# 10_-_RFID.net
KiCad netlist of a schematic drawn in Altium Designer
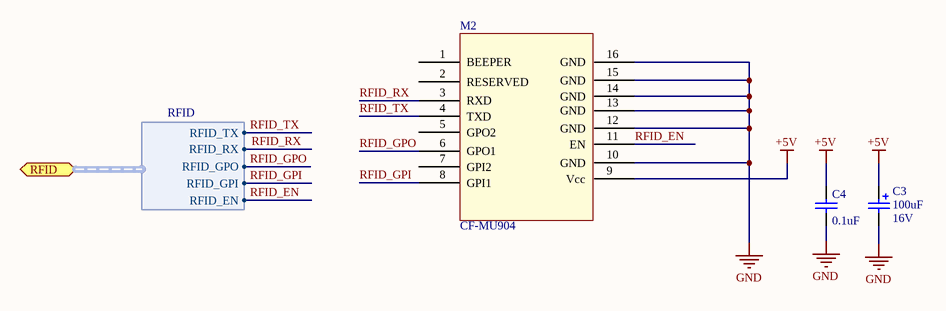
[diagram p0: [10] - RFID.SchDoc]

(export (version "E")
  (design (tool "Eeschema 10.0.6"))
  (components
    (comp (ref "C3")
      (value "Capacitor Polarized")
      (footprint "Tantalum 3216 A")
      (description "Tantalum Capacitor")
      (fields
        (field (name "MANUFACTURER") "Kemet")
        (field (name "MANUFACTURER PART NUMBER") "T491A106K016AT")
        (field (name "CAPACITANCE") "100uF")
        (field (name "VOLTAGE - RATED") "16V")
      )
      (libsource (lib "Altium_Library") (part "Capacitor Polarized"))
    )
    (comp (ref "C4")
      (value "0.1uF")
      (footprint "Cap 0603")
      (description "Capacitor 0603 CER")
      (fields
        (field (name "MANUFACTURER") "Kemet")
        (field (name "MANUFACTURER PART NUMBER") "C0603C473K5RACTU")
      )
      (libsource (lib "Altium_Library") (part "Capacitor"))
    )
    (comp (ref "M2") (value "CF-MU904") (libsource (lib "Blue Tractor-2021") (part "CF-MU904")))
  )
  (nets
    (net (code "2") (name "+5V") (class "Default")
      (node (ref "C3") (pin "1") (pinfunction "1_1") (pintype "passive"))
      (node (ref "C4") (pin "2") (pinfunction "2_2") (pintype "passive"))
      (node (ref "M2") (pin "9") (pinfunction "Vcc_9") (pintype "power_in"))
    )
    (net (code "3") (name "/RFID_EN") (class "Default")
      (node (ref "M2") (pin "11") (pinfunction "EN_11") (pintype "power_in"))
    )
    (net (code "4") (name "/RFID_GPI") (class "Default")
      (node (ref "M2") (pin "8") (pinfunction "GPI1_8") (pintype "passive"))
    )
    (net (code "5") (name "/RFID_GPO") (class "Default")
      (node (ref "M2") (pin "6") (pinfunction "GPO1_6") (pintype "passive"))
    )
    (net (code "6") (name "/RFID_RX") (class "Default")
      (node (ref "M2") (pin "3") (pinfunction "RXD_3") (pintype "passive"))
    )
    (net (code "7") (name "/RFID_TX") (class "Default")
      (node (ref "M2") (pin "4") (pinfunction "TXD_4") (pintype "passive"))
    )
    (net (code "9") (name "GND") (class "Default")
      (node (ref "C3") (pin "2") (pinfunction "2_2") (pintype "passive"))
      (node (ref "C4") (pin "1") (pinfunction "1_1") (pintype "passive"))
      (node (ref "M2") (pin "10") (pinfunction "GND_10") (pintype "power_in"))
      (node (ref "M2") (pin "12") (pinfunction "GND_12") (pintype "power_in"))
      (node (ref "M2") (pin "13") (pinfunction "GND_13") (pintype "power_in"))
      (node (ref "M2") (pin "14") (pinfunction "GND_14") (pintype "power_in"))
      (node (ref "M2") (pin "15") (pinfunction "GND_15") (pintype "power_in"))
      (node (ref "M2") (pin "16") (pinfunction "GND_16") (pintype "power_in"))
    )
    (net (code "10") (name "unconnected-(M2-BEEPER-Pad1)") (class "Default")
      (node (ref "M2") (pin "1") (pinfunction "BEEPER_1") (pintype "power_in"))
    )
    (net (code "11") (name "unconnected-(M2-GPI2-Pad7)") (class "Default")
      (node (ref "M2") (pin "7") (pinfunction "GPI2_7") (pintype "passive"))
    )
    (net (code "12") (name "unconnected-(M2-GPO2-Pad5)") (class "Default")
      (node (ref "M2") (pin "5") (pinfunction "GPO2_5") (pintype "passive"))
    )
    (net (code "13") (name "unconnected-(M2-RESERVED-Pad2)") (class "Default")
      (node (ref "M2") (pin "2") (pinfunction "RESERVED_2") (pintype "passive"))
    )
  )
)
